# pca10040_sheet3_buttons_and_leds.net
KiCad netlist of a schematic drawn in Altium Designer
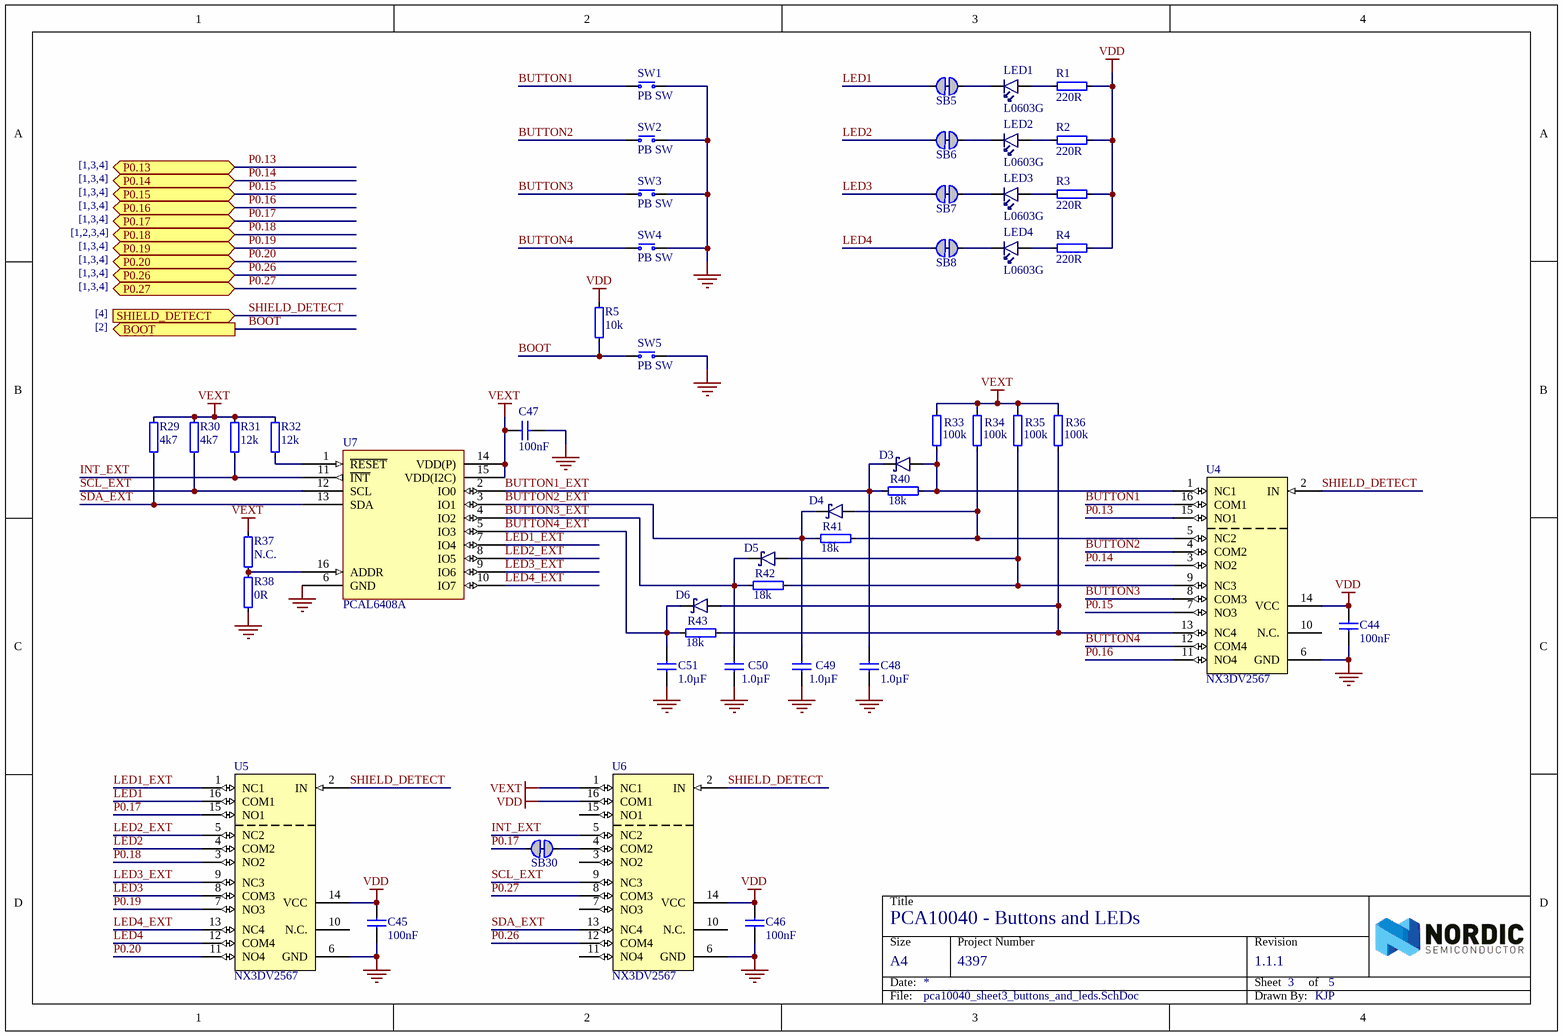
[diagram p0: pca10040_sheet3_buttons_and_leds.SchDoc]

(export (version "E")
  (design (tool "Eeschema 10.0.6"))
  (components
    (comp (ref "C44")
      (value "100nF")
      (footprint "CAPC1005X04L")
      (description "Capacitor, X7R, ±10%")
      (fields (field (name "PART NUMBER") "C0402-100n") (field (name "PUBLISHER") "Nordic Semiconductor"))
      (libsource (lib "Nordic Passive DB") (part "CAP"))
    )
    (comp (ref "C45")
      (value "100nF")
      (footprint "CAPC1005X04L")
      (description "Capacitor, X7R, ±10%")
      (fields (field (name "PART NUMBER") "C0402-100n") (field (name "PUBLISHER") "Nordic Semiconductor"))
      (libsource (lib "Nordic Passive DB") (part "CAP"))
    )
    (comp (ref "C46")
      (value "100nF")
      (footprint "CAPC1005X04L")
      (description "Capacitor, X7R, ±10%")
      (fields (field (name "PART NUMBER") "C0402-100n") (field (name "PUBLISHER") "Nordic Semiconductor"))
      (libsource (lib "Nordic Passive DB") (part "CAP"))
    )
    (comp (ref "C47")
      (value "100nF")
      (footprint "CAPC1005X04L")
      (description "Capacitor, X7R, ±10%")
      (fields (field (name "PART NUMBER") "C0402-100n") (field (name "PUBLISHER") "Nordic Semiconductor"))
      (libsource (lib "Nordic Passive DB") (part "CAP"))
    )
    (comp (ref "C48")
      (value "1.0µF")
      (footprint "CAPC1005X04L")
      (description "Capacitor, X5R, ±5%")
      (fields (field (name "PART NUMBER") "C0402-1µ0") (field (name "PUBLISHER") "Nordic Semiconductor"))
      (libsource (lib "Nordic Passive DB") (part "CAP"))
    )
    (comp (ref "C49")
      (value "1.0µF")
      (footprint "CAPC1005X04L")
      (description "Capacitor, X5R, ±5%")
      (fields (field (name "PART NUMBER") "C0402-1µ0") (field (name "PUBLISHER") "Nordic Semiconductor"))
      (libsource (lib "Nordic Passive DB") (part "CAP"))
    )
    (comp (ref "C50")
      (value "1.0µF")
      (footprint "CAPC1005X04L")
      (description "Capacitor, X5R, ±5%")
      (fields (field (name "PART NUMBER") "C0402-1µ0") (field (name "PUBLISHER") "Nordic Semiconductor"))
      (libsource (lib "Nordic Passive DB") (part "CAP"))
    )
    (comp (ref "C51")
      (value "1.0µF")
      (footprint "CAPC1005X04L")
      (description "Capacitor, X5R, ±5%")
      (fields (field (name "PART NUMBER") "C0402-1µ0") (field (name "PUBLISHER") "Nordic Semiconductor"))
      (libsource (lib "Nordic Passive DB") (part "CAP"))
    )
    (comp (ref "D3")
      (value "1PS79SB30.115")
      (footprint "SOD-523")
      (description "Diode Schottky Vf=0.38, Vr=40V, If=200mA, Ir=500nA")
      (fields (field (name "MANUFACTURER") "NXP") (field (name "PUBLISHER") "Nordic Semiconductor"))
      (libsource (lib "Nordic Discrete DB") (part "D{colon}SCHOTTKY"))
    )
    (comp (ref "D4")
      (value "1PS79SB30.115")
      (footprint "SOD-523")
      (description "Diode Schottky Vf=0.38, Vr=40V, If=200mA, Ir=500nA")
      (fields (field (name "MANUFACTURER") "NXP") (field (name "PUBLISHER") "Nordic Semiconductor"))
      (libsource (lib "Nordic Discrete DB") (part "D{colon}SCHOTTKY"))
    )
    (comp (ref "D5")
      (value "1PS79SB30.115")
      (footprint "SOD-523")
      (description "Diode Schottky Vf=0.38, Vr=40V, If=200mA, Ir=500nA")
      (fields (field (name "MANUFACTURER") "NXP") (field (name "PUBLISHER") "Nordic Semiconductor"))
      (libsource (lib "Nordic Discrete DB") (part "D{colon}SCHOTTKY"))
    )
    (comp (ref "D6")
      (value "1PS79SB30.115")
      (footprint "SOD-523")
      (description "Diode Schottky Vf=0.38, Vr=40V, If=200mA, Ir=500nA")
      (fields (field (name "MANUFACTURER") "NXP") (field (name "PUBLISHER") "Nordic Semiconductor"))
      (libsource (lib "Nordic Discrete DB") (part "D{colon}SCHOTTKY"))
    )
    (comp (ref "LED1")
      (value "L0603G")
      (footprint "LED_0603_G")
      (description "LED SMARTLED GREEN 570NM 0603")
      (fields
        (field (name "PART NUMBER") "LG L29K Smartled Green")
        (field (name "MANUFACTURER") "Multicomp")
        (field (name "PUBLISHER") "Nordic Semiconductor")
      )
      (libsource (lib "Nordic Discrete DB") (part "D{colon}LED"))
    )
    (comp (ref "LED2")
      (value "L0603G")
      (footprint "LED_0603_G")
      (description "LED SMARTLED GREEN 570NM 0603")
      (fields
        (field (name "PART NUMBER") "LG L29K Smartled Green")
        (field (name "MANUFACTURER") "Multicomp")
        (field (name "PUBLISHER") "Nordic Semiconductor")
      )
      (libsource (lib "Nordic Discrete DB") (part "D{colon}LED"))
    )
    (comp (ref "LED3")
      (value "L0603G")
      (footprint "LED_0603_G")
      (description "LED SMARTLED GREEN 570NM 0603")
      (fields
        (field (name "PART NUMBER") "LG L29K Smartled Green")
        (field (name "MANUFACTURER") "Multicomp")
        (field (name "PUBLISHER") "Nordic Semiconductor")
      )
      (libsource (lib "Nordic Discrete DB") (part "D{colon}LED"))
    )
    (comp (ref "LED4")
      (value "L0603G")
      (footprint "LED_0603_G")
      (description "LED SMARTLED GREEN 570NM 0603")
      (fields
        (field (name "PART NUMBER") "LG L29K Smartled Green")
        (field (name "MANUFACTURER") "Multicomp")
        (field (name "PUBLISHER") "Nordic Semiconductor")
      )
      (libsource (lib "Nordic Discrete DB") (part "D{colon}LED"))
    )
    (comp (ref "R1")
      (value "220R")
      (footprint "RESC1005X04L")
      (description "Resistor, ±1%, 0.063W")
      (fields (field (name "PART NUMBER") "R0402-220") (field (name "PUBLISHER") "Nordic Semiconductor"))
      (libsource (lib "Nordic Passive DB") (part "RES_1"))
    )
    (comp (ref "R2")
      (value "220R")
      (footprint "RESC1005X04L")
      (description "Resistor, ±1%, 0.063W")
      (fields (field (name "PART NUMBER") "R0402-220") (field (name "PUBLISHER") "Nordic Semiconductor"))
      (libsource (lib "Nordic Passive DB") (part "RES_1"))
    )
    (comp (ref "R3")
      (value "220R")
      (footprint "RESC1005X04L")
      (description "Resistor, ±1%, 0.063W")
      (fields (field (name "PART NUMBER") "R0402-220") (field (name "PUBLISHER") "Nordic Semiconductor"))
      (libsource (lib "Nordic Passive DB") (part "RES_1"))
    )
    (comp (ref "R4")
      (value "220R")
      (footprint "RESC1005X04L")
      (description "Resistor, ±1%, 0.063W")
      (fields (field (name "PART NUMBER") "R0402-220") (field (name "PUBLISHER") "Nordic Semiconductor"))
      (libsource (lib "Nordic Passive DB") (part "RES_1"))
    )
    (comp (ref "R5")
      (value "10k")
      (footprint "RESC1005X04L")
      (description "Resistor, ±1%, 0.063W")
      (fields (field (name "PART NUMBER") "R0402-10k") (field (name "PUBLISHER") "Nordic Semiconductor"))
      (libsource (lib "Nordic Passive DB") (part "RES_1"))
    )
    (comp (ref "R29")
      (value "4k7")
      (footprint "RESC1005X04L")
      (description "Resistor, ±1%, 0.063W")
      (fields (field (name "PART NUMBER") "R0402-4k7") (field (name "PUBLISHER") "Nordic Semiconductor"))
      (libsource (lib "Nordic Passive DB") (part "RES_1"))
    )
    (comp (ref "R30")
      (value "4k7")
      (footprint "RESC1005X04L")
      (description "Resistor, ±1%, 0.063W")
      (fields (field (name "PART NUMBER") "R0402-4k7") (field (name "PUBLISHER") "Nordic Semiconductor"))
      (libsource (lib "Nordic Passive DB") (part "RES_1"))
    )
    (comp (ref "R31")
      (value "12k")
      (footprint "RESC1005X04L")
      (description "Resistor, ±1%, 0.063W")
      (fields (field (name "PART NUMBER") "R0402-12k") (field (name "PUBLISHER") "Nordic Semiconductor"))
      (libsource (lib "Nordic Passive DB") (part "RES_1"))
    )
    (comp (ref "R32")
      (value "12k")
      (footprint "RESC1005X04L")
      (description "Resistor, ±1%, 0.063W")
      (fields (field (name "PART NUMBER") "R0402-12k") (field (name "PUBLISHER") "Nordic Semiconductor"))
      (libsource (lib "Nordic Passive DB") (part "RES_1"))
    )
    (comp (ref "R33")
      (value "100k")
      (footprint "RESC1005X04L")
      (description "Resistor, ±1%, 0.063W")
      (fields (field (name "PART NUMBER") "R0402-100k") (field (name "PUBLISHER") "Nordic Semiconductor"))
      (libsource (lib "Nordic Passive DB") (part "RES_1"))
    )
    (comp (ref "R34")
      (value "100k")
      (footprint "RESC1005X04L")
      (description "Resistor, ±1%, 0.063W")
      (fields (field (name "PART NUMBER") "R0402-100k") (field (name "PUBLISHER") "Nordic Semiconductor"))
      (libsource (lib "Nordic Passive DB") (part "RES_1"))
    )
    (comp (ref "R35")
      (value "100k")
      (footprint "RESC1005X04L")
      (description "Resistor, ±1%, 0.063W")
      (fields (field (name "PART NUMBER") "R0402-100k") (field (name "PUBLISHER") "Nordic Semiconductor"))
      (libsource (lib "Nordic Passive DB") (part "RES_1"))
    )
    (comp (ref "R36")
      (value "100k")
      (footprint "RESC1005X04L")
      (description "Resistor, ±1%, 0.063W")
      (fields (field (name "PART NUMBER") "R0402-100k") (field (name "PUBLISHER") "Nordic Semiconductor"))
      (libsource (lib "Nordic Passive DB") (part "RES_1"))
    )
    (comp (ref "R37")
      (value "N.C.")
      (footprint "RESC1005X04L")
      (description "Not mounted")
      (fields (field (name "PART NUMBER") "R0402-N.C.") (field (name "PUBLISHER") "Nordic Semiconductor"))
      (libsource (lib "Nordic Passive DB") (part "RES_1"))
    )
    (comp (ref "R38")
      (value "0R")
      (footprint "RESC1005X04L")
      (description "Resistor, ±5%, 0.063W")
      (fields (field (name "PART NUMBER") "R0402-0R") (field (name "PUBLISHER") "Nordic Semiconductor"))
      (libsource (lib "Nordic Passive DB") (part "RES_1"))
    )
    (comp (ref "R40")
      (value "18k")
      (footprint "RESC1005X04L")
      (description "Resistor, ±1%, 0.063W")
      (fields (field (name "PART NUMBER") "R0402-18k") (field (name "PUBLISHER") "Nordic Semiconductor"))
      (libsource (lib "Nordic Passive DB") (part "RES_1"))
    )
    (comp (ref "R41")
      (value "18k")
      (footprint "RESC1005X04L")
      (description "Resistor, ±1%, 0.063W")
      (fields (field (name "PART NUMBER") "R0402-18k") (field (name "PUBLISHER") "Nordic Semiconductor"))
      (libsource (lib "Nordic Passive DB") (part "RES_1"))
    )
    (comp (ref "R42")
      (value "18k")
      (footprint "RESC1005X04L")
      (description "Resistor, ±1%, 0.063W")
      (fields (field (name "PART NUMBER") "R0402-18k") (field (name "PUBLISHER") "Nordic Semiconductor"))
      (libsource (lib "Nordic Passive DB") (part "RES_1"))
    )
    (comp (ref "R43")
      (value "18k")
      (footprint "RESC1005X04L")
      (description "Resistor, ±1%, 0.063W")
      (fields (field (name "PART NUMBER") "R0402-18k") (field (name "PUBLISHER") "Nordic Semiconductor"))
      (libsource (lib "Nordic Passive DB") (part "RES_1"))
    )
    (comp (ref "SB5")
      (value "Solderbridge")
      (footprint "Solderbridge_Shorted")
      (description "Shorted Solderbridge")
      (fields
        (field (name "PART NUMBER") "Solderbridge Shorted")
        (field (name "PUBLISHER") "Nordic Semiconductor")
      )
      (libsource (lib "Nordic Passive DB") (part "SOLDERBRIDGE_SHORTED"))
    )
    (comp (ref "SB6")
      (value "Solderbridge")
      (footprint "Solderbridge_Shorted")
      (description "Shorted Solderbridge")
      (fields
        (field (name "PART NUMBER") "Solderbridge Shorted")
        (field (name "PUBLISHER") "Nordic Semiconductor")
      )
      (libsource (lib "Nordic Passive DB") (part "SOLDERBRIDGE_SHORTED"))
    )
    (comp (ref "SB7")
      (value "Solderbridge")
      (footprint "Solderbridge_Shorted")
      (description "Shorted Solderbridge")
      (fields
        (field (name "PART NUMBER") "Solderbridge Shorted")
        (field (name "PUBLISHER") "Nordic Semiconductor")
      )
      (libsource (lib "Nordic Passive DB") (part "SOLDERBRIDGE_SHORTED"))
    )
    (comp (ref "SB8")
      (value "Solderbridge")
      (footprint "Solderbridge_Shorted")
      (description "Shorted Solderbridge")
      (fields
        (field (name "PART NUMBER") "Solderbridge Shorted")
        (field (name "PUBLISHER") "Nordic Semiconductor")
      )
      (libsource (lib "Nordic Passive DB") (part "SOLDERBRIDGE_SHORTED"))
    )
    (comp (ref "SB30")
      (value "Solderbridge")
      (footprint "Solderbridge_Shorted")
      (description "Shorted Solderbridge")
      (fields
        (field (name "PART NUMBER") "Solderbridge Shorted")
        (field (name "PUBLISHER") "Nordic Semiconductor")
      )
      (libsource (lib "Nordic Passive DB") (part "SOLDERBRIDGE_SHORTED"))
    )
    (comp (ref "SW1")
      (value "PB SW")
      (footprint "Switch-PB-6.2x6.3mm-SMD")
      (description "Tactile Switch, SPNO, SMD, 160gf, 6.2x6.3x2.5mm")
      (fields
        (field (name "PART NUMBER") "Switch-PB-6.2x6.3mm-SMD")
        (field (name "MANUFACTURER") "Dailywell")
        (field (name "PUBLISHER") "Nordic Semiconductor")
      )
      (libsource (lib "Nordic Discrete DB") (part "SW-PB"))
    )
    (comp (ref "SW2")
      (value "PB SW")
      (footprint "Switch-PB-6.2x6.3mm-SMD")
      (description "Tactile Switch, SPNO, SMD, 160gf, 6.2x6.3x2.5mm")
      (fields
        (field (name "PART NUMBER") "Switch-PB-6.2x6.3mm-SMD")
        (field (name "MANUFACTURER") "Dailywell")
        (field (name "PUBLISHER") "Nordic Semiconductor")
      )
      (libsource (lib "Nordic Discrete DB") (part "SW-PB"))
    )
    (comp (ref "SW3")
      (value "PB SW")
      (footprint "Switch-PB-6.2x6.3mm-SMD")
      (description "Tactile Switch, SPNO, SMD, 160gf, 6.2x6.3x2.5mm")
      (fields
        (field (name "PART NUMBER") "Switch-PB-6.2x6.3mm-SMD")
        (field (name "MANUFACTURER") "Dailywell")
        (field (name "PUBLISHER") "Nordic Semiconductor")
      )
      (libsource (lib "Nordic Discrete DB") (part "SW-PB"))
    )
    (comp (ref "SW4")
      (value "PB SW")
      (footprint "Switch-PB-6.2x6.3mm-SMD")
      (description "Tactile Switch, SPNO, SMD, 160gf, 6.2x6.3x2.5mm")
      (fields
        (field (name "PART NUMBER") "Switch-PB-6.2x6.3mm-SMD")
        (field (name "MANUFACTURER") "Dailywell")
        (field (name "PUBLISHER") "Nordic Semiconductor")
      )
      (libsource (lib "Nordic Discrete DB") (part "SW-PB"))
    )
    (comp (ref "SW5")
      (value "PB SW")
      (footprint "Switch-PB-6.2x6.3mm-SMD")
      (description "Tactile Switch, SPNO, SMD, 160gf, 6.2x6.3x2.5mm")
      (fields
        (field (name "PART NUMBER") "Switch-PB-6.2x6.3mm-SMD")
        (field (name "MANUFACTURER") "Dailywell")
        (field (name "PUBLISHER") "Nordic Semiconductor")
      )
      (libsource (lib "Nordic Discrete DB") (part "SW-PB"))
    )
    (comp (ref "U4")
      (value "NX3DV2567")
      (footprint "XQFN40P180X260X50-16N")
      (description "Low-ohmic four-pole double-throw analog switch")
      (fields
        (field (name "PART NUMBER") "NX3DV2567GU")
        (field (name "MANUFACTURER") "NXP Semiconductors")
        (field (name "PUBLISHER") "Nordic Semiconductor")
      )
      (libsource (lib "Nordic Active DB") (part "NX3DV2567"))
    )
    (comp (ref "U5")
      (value "NX3DV2567")
      (footprint "XQFN40P180X260X50-16N")
      (description "Low-ohmic four-pole double-throw analog switch")
      (fields
        (field (name "PART NUMBER") "NX3DV2567GU")
        (field (name "MANUFACTURER") "NXP Semiconductors")
        (field (name "PUBLISHER") "Nordic Semiconductor")
      )
      (libsource (lib "Nordic Active DB") (part "NX3DV2567"))
    )
    (comp (ref "U6")
      (value "NX3DV2567")
      (footprint "XQFN40P180X260X50-16N")
      (description "Low-ohmic four-pole double-throw analog switch")
      (fields
        (field (name "PART NUMBER") "NX3DV2567GU")
        (field (name "MANUFACTURER") "NXP Semiconductors")
        (field (name "PUBLISHER") "Nordic Semiconductor")
      )
      (libsource (lib "Nordic Active DB") (part "NX3DV2567"))
    )
    (comp (ref "U7")
      (value "PCAL6408A")
      (footprint "XQFN40P180X260X50-16N")
      (description "8-bit I2C-bus I/O expander with interrupt output")
      (fields
        (field (name "PART NUMBER") "PCAL6408AHK")
        (field (name "MANUFACTURER") "NXP Semiconductors")
        (field (name "PUBLISHER") "Nordic Semiconductor")
      )
      (libsource (lib "Nordic Active DB") (part "PCAL6408AHK"))
    )
  )
  (nets
    (net (code "1") (name "/BOOT") (class "Default")
      (node (ref "R5") (pin "1") (pinfunction "1_1") (pintype "passive"))
      (node (ref "SW5") (pin "2") (pinfunction "COM_2") (pintype "passive"))
    )
    (net (code "2") (name "/BUTTON1") (class "Default")
      (node (ref "SW1") (pin "2") (pinfunction "COM_2") (pintype "passive"))
      (node (ref "U4") (pin "16") (pinfunction "COM1_16") (pintype "bidirectional"))
    )
    (net (code "3") (name "/BUTTON1_EXT") (class "Default")
      (node (ref "C48") (pin "1") (pinfunction "1_1") (pintype "passive"))
      (node (ref "D3") (pin "3") (pinfunction "C_3") (pintype "passive"))
      (node (ref "R40") (pin "1") (pinfunction "1_1") (pintype "passive"))
      (node (ref "U7") (pin "2") (pinfunction "IO0_2") (pintype "bidirectional"))
    )
    (net (code "4") (name "/BUTTON2") (class "Default")
      (node (ref "SW2") (pin "2") (pinfunction "COM_2") (pintype "passive"))
      (node (ref "U4") (pin "4") (pinfunction "COM2_4") (pintype "bidirectional"))
    )
    (net (code "5") (name "/BUTTON2_EXT") (class "Default")
      (node (ref "C49") (pin "2") (pinfunction "2_2") (pintype "passive"))
      (node (ref "D4") (pin "3") (pinfunction "C_3") (pintype "passive"))
      (node (ref "R41") (pin "1") (pinfunction "1_1") (pintype "passive"))
      (node (ref "U7") (pin "3") (pinfunction "IO1_3") (pintype "bidirectional"))
    )
    (net (code "6") (name "/BUTTON3") (class "Default")
      (node (ref "SW3") (pin "2") (pinfunction "COM_2") (pintype "passive"))
      (node (ref "U4") (pin "8") (pinfunction "COM3_8") (pintype "bidirectional"))
    )
    (net (code "7") (name "/BUTTON3_EXT") (class "Default")
      (node (ref "C50") (pin "2") (pinfunction "2_2") (pintype "passive"))
      (node (ref "D5") (pin "3") (pinfunction "C_3") (pintype "passive"))
      (node (ref "R42") (pin "1") (pinfunction "1_1") (pintype "passive"))
      (node (ref "U7") (pin "4") (pinfunction "IO2_4") (pintype "bidirectional"))
    )
    (net (code "8") (name "/BUTTON4") (class "Default")
      (node (ref "SW4") (pin "2") (pinfunction "COM_2") (pintype "passive"))
      (node (ref "U4") (pin "12") (pinfunction "COM4_12") (pintype "bidirectional"))
    )
    (net (code "9") (name "/BUTTON4_EXT") (class "Default")
      (node (ref "C51") (pin "1") (pinfunction "1_1") (pintype "passive"))
      (node (ref "D6") (pin "3") (pinfunction "C_3") (pintype "passive"))
      (node (ref "R43") (pin "1") (pinfunction "1_1") (pintype "passive"))
      (node (ref "U7") (pin "5") (pinfunction "IO3_5") (pintype "bidirectional"))
    )
    (net (code "10") (name "/INT_EXT") (class "Default")
      (node (ref "R31") (pin "1") (pinfunction "1_1") (pintype "passive"))
      (node (ref "U6") (pin "5") (pinfunction "NC2_5") (pintype "bidirectional"))
      (node (ref "U7") (pin "11") (pinfunction "~{INT}_11") (pintype "output"))
    )
    (net (code "11") (name "/LED1") (class "Default")
      (node (ref "SB5") (pin "1") (pinfunction "0_1") (pintype "passive"))
      (node (ref "U5") (pin "16") (pinfunction "COM1_16") (pintype "bidirectional"))
    )
    (net (code "12") (name "/LED1_EXT") (class "Default")
      (node (ref "U5") (pin "1") (pinfunction "NC1_1") (pintype "bidirectional"))
      (node (ref "U7") (pin "7") (pinfunction "IO4_7") (pintype "bidirectional"))
    )
    (net (code "13") (name "/LED2") (class "Default")
      (node (ref "SB6") (pin "1") (pinfunction "0_1") (pintype "passive"))
      (node (ref "U5") (pin "4") (pinfunction "COM2_4") (pintype "bidirectional"))
    )
    (net (code "14") (name "/LED2_EXT") (class "Default")
      (node (ref "U5") (pin "5") (pinfunction "NC2_5") (pintype "bidirectional"))
      (node (ref "U7") (pin "8") (pinfunction "IO5_8") (pintype "bidirectional"))
    )
    (net (code "15") (name "/LED3") (class "Default")
      (node (ref "SB7") (pin "1") (pinfunction "0_1") (pintype "passive"))
      (node (ref "U5") (pin "8") (pinfunction "COM3_8") (pintype "bidirectional"))
    )
    (net (code "16") (name "/LED3_EXT") (class "Default")
      (node (ref "U5") (pin "9") (pinfunction "NC3_9") (pintype "bidirectional"))
      (node (ref "U7") (pin "9") (pinfunction "IO6_9") (pintype "bidirectional"))
    )
    (net (code "17") (name "/LED4") (class "Default")
      (node (ref "SB8") (pin "1") (pinfunction "0_1") (pintype "passive"))
      (node (ref "U5") (pin "12") (pinfunction "COM4_12") (pintype "bidirectional"))
    )
    (net (code "18") (name "/LED4_EXT") (class "Default")
      (node (ref "U5") (pin "13") (pinfunction "NC4_13") (pintype "bidirectional"))
      (node (ref "U7") (pin "10") (pinfunction "IO7_10") (pintype "bidirectional"))
    )
    (net (code "19") (name "/P0.13") (class "Default")
      (node (ref "U4") (pin "15") (pinfunction "NO1_15") (pintype "bidirectional"))
    )
    (net (code "20") (name "/P0.14") (class "Default")
      (node (ref "U4") (pin "3") (pinfunction "NO2_3") (pintype "bidirectional"))
    )
    (net (code "21") (name "/P0.15") (class "Default")
      (node (ref "U4") (pin "7") (pinfunction "NO3_7") (pintype "bidirectional"))
    )
    (net (code "22") (name "/P0.16") (class "Default")
      (node (ref "U4") (pin "11") (pinfunction "NO4_11") (pintype "bidirectional"))
    )
    (net (code "23") (name "/P0.17") (class "Default")
      (node (ref "SB30") (pin "1") (pinfunction "0_1") (pintype "passive"))
      (node (ref "U5") (pin "15") (pinfunction "NO1_15") (pintype "bidirectional"))
    )
    (net (code "24") (name "/P0.18") (class "Default")
      (node (ref "U5") (pin "3") (pinfunction "NO2_3") (pintype "bidirectional"))
    )
    (net (code "25") (name "/P0.19") (class "Default")
      (node (ref "U5") (pin "7") (pinfunction "NO3_7") (pintype "bidirectional"))
    )
    (net (code "26") (name "/P0.20") (class "Default")
      (node (ref "U5") (pin "11") (pinfunction "NO4_11") (pintype "bidirectional"))
    )
    (net (code "27") (name "/P0.26") (class "Default")
      (node (ref "U6") (pin "12") (pinfunction "COM4_12") (pintype "bidirectional"))
    )
    (net (code "28") (name "/P0.27") (class "Default")
      (node (ref "U6") (pin "8") (pinfunction "COM3_8") (pintype "bidirectional"))
    )
    (net (code "29") (name "/SCL_EXT") (class "Default")
      (node (ref "R30") (pin "1") (pinfunction "1_1") (pintype "passive"))
      (node (ref "U6") (pin "9") (pinfunction "NC3_9") (pintype "bidirectional"))
      (node (ref "U7") (pin "12") (pinfunction "SCL_12") (pintype "power_in"))
    )
    (net (code "30") (name "/SDA_EXT") (class "Default")
      (node (ref "R29") (pin "1") (pinfunction "1_1") (pintype "passive"))
      (node (ref "U6") (pin "13") (pinfunction "NC4_13") (pintype "bidirectional"))
      (node (ref "U7") (pin "13") (pinfunction "SDA_13") (pintype "passive"))
    )
    (net (code "31") (name "/SHIELD_DETECT") (class "Default")
      (node (ref "U4") (pin "2") (pinfunction "IN_2") (pintype "input"))
      (node (ref "U5") (pin "2") (pinfunction "IN_2") (pintype "input"))
      (node (ref "U6") (pin "2") (pinfunction "IN_2") (pintype "input"))
    )
    (net (code "32") (name "GND") (class "Default")
      (node (ref "C44") (pin "1") (pinfunction "1_1") (pintype "passive"))
      (node (ref "C45") (pin "1") (pinfunction "1_1") (pintype "passive"))
      (node (ref "C46") (pin "1") (pinfunction "1_1") (pintype "passive"))
      (node (ref "C47") (pin "1") (pinfunction "1_1") (pintype "passive"))
      (node (ref "C48") (pin "2") (pinfunction "2_2") (pintype "passive"))
      (node (ref "C49") (pin "1") (pinfunction "1_1") (pintype "passive"))
      (node (ref "C50") (pin "1") (pinfunction "1_1") (pintype "passive"))
      (node (ref "C51") (pin "2") (pinfunction "2_2") (pintype "passive"))
      (node (ref "R38") (pin "1") (pinfunction "1_1") (pintype "passive"))
      (node (ref "SW1") (pin "1") (pinfunction "N.O_1") (pintype "passive"))
      (node (ref "SW2") (pin "1") (pinfunction "N.O_1") (pintype "passive"))
      (node (ref "SW3") (pin "1") (pinfunction "N.O_1") (pintype "passive"))
      (node (ref "SW4") (pin "1") (pinfunction "N.O_1") (pintype "passive"))
      (node (ref "SW5") (pin "1") (pinfunction "N.O_1") (pintype "passive"))
      (node (ref "U4") (pin "6") (pinfunction "GND_6") (pintype "power_in"))
      (node (ref "U5") (pin "6") (pinfunction "GND_6") (pintype "power_in"))
      (node (ref "U6") (pin "6") (pinfunction "GND_6") (pintype "power_in"))
      (node (ref "U7") (pin "6") (pinfunction "GND_6") (pintype "power_in"))
    )
    (net (code "33") (name "Net-(D3-A)") (class "Default")
      (node (ref "D3") (pin "1") (pinfunction "A_1") (pintype "passive"))
      (node (ref "R33") (pin "1") (pinfunction "1_1") (pintype "passive"))
      (node (ref "R40") (pin "2") (pinfunction "2_2") (pintype "passive"))
      (node (ref "U4") (pin "1") (pinfunction "NC1_1") (pintype "bidirectional"))
    )
    (net (code "34") (name "Net-(D4-A)") (class "Default")
      (node (ref "D4") (pin "1") (pinfunction "A_1") (pintype "passive"))
      (node (ref "R34") (pin "1") (pinfunction "1_1") (pintype "passive"))
      (node (ref "R41") (pin "2") (pinfunction "2_2") (pintype "passive"))
      (node (ref "U4") (pin "5") (pinfunction "NC2_5") (pintype "bidirectional"))
    )
    (net (code "35") (name "Net-(D5-A)") (class "Default")
      (node (ref "D5") (pin "1") (pinfunction "A_1") (pintype "passive"))
      (node (ref "R35") (pin "1") (pinfunction "1_1") (pintype "passive"))
      (node (ref "R42") (pin "2") (pinfunction "2_2") (pintype "passive"))
      (node (ref "U4") (pin "9") (pinfunction "NC3_9") (pintype "bidirectional"))
    )
    (net (code "36") (name "Net-(D6-A)") (class "Default")
      (node (ref "D6") (pin "1") (pinfunction "A_1") (pintype "passive"))
      (node (ref "R36") (pin "1") (pinfunction "1_1") (pintype "passive"))
      (node (ref "R43") (pin "2") (pinfunction "2_2") (pintype "passive"))
      (node (ref "U4") (pin "13") (pinfunction "NC4_13") (pintype "bidirectional"))
    )
    (net (code "37") (name "Net-(LED1-A)") (class "Default")
      (node (ref "LED1") (pin "2") (pinfunction "A_2") (pintype "passive"))
      (node (ref "R1") (pin "1") (pinfunction "1_1") (pintype "passive"))
    )
    (net (code "38") (name "Net-(LED1-C)") (class "Default")
      (node (ref "LED1") (pin "1") (pinfunction "C_1") (pintype "passive"))
      (node (ref "SB5") (pin "2") (pinfunction "1_2") (pintype "passive"))
    )
    (net (code "39") (name "Net-(LED2-A)") (class "Default")
      (node (ref "LED2") (pin "2") (pinfunction "A_2") (pintype "passive"))
      (node (ref "R2") (pin "1") (pinfunction "1_1") (pintype "passive"))
    )
    (net (code "40") (name "Net-(LED2-C)") (class "Default")
      (node (ref "LED2") (pin "1") (pinfunction "C_1") (pintype "passive"))
      (node (ref "SB6") (pin "2") (pinfunction "1_2") (pintype "passive"))
    )
    (net (code "41") (name "Net-(LED3-A)") (class "Default")
      (node (ref "LED3") (pin "2") (pinfunction "A_2") (pintype "passive"))
      (node (ref "R3") (pin "1") (pinfunction "1_1") (pintype "passive"))
    )
    (net (code "42") (name "Net-(LED3-C)") (class "Default")
      (node (ref "LED3") (pin "1") (pinfunction "C_1") (pintype "passive"))
      (node (ref "SB7") (pin "2") (pinfunction "1_2") (pintype "passive"))
    )
    (net (code "43") (name "Net-(LED4-A)") (class "Default")
      (node (ref "LED4") (pin "2") (pinfunction "A_2") (pintype "passive"))
      (node (ref "R4") (pin "1") (pinfunction "1_1") (pintype "passive"))
    )
    (net (code "44") (name "Net-(LED4-C)") (class "Default")
      (node (ref "LED4") (pin "1") (pinfunction "C_1") (pintype "passive"))
      (node (ref "SB8") (pin "2") (pinfunction "1_2") (pintype "passive"))
    )
    (net (code "45") (name "Net-(SB30-1)") (class "Default")
      (node (ref "SB30") (pin "2") (pinfunction "1_2") (pintype "passive"))
      (node (ref "U6") (pin "4") (pinfunction "COM2_4") (pintype "bidirectional"))
    )
    (net (code "46") (name "Net-(U7-ADDR)") (class "Default")
      (node (ref "R37") (pin "1") (pinfunction "1_1") (pintype "passive"))
      (node (ref "R38") (pin "2") (pinfunction "2_2") (pintype "passive"))
      (node (ref "U7") (pin "16") (pinfunction "ADDR_16") (pintype "input"))
    )
    (net (code "47") (name "Net-(U7-~{RESET})") (class "Default")
      (node (ref "R32") (pin "1") (pinfunction "1_1") (pintype "passive"))
      (node (ref "U7") (pin "1") (pinfunction "~{RESET}_1") (pintype "input"))
    )
    (net (code "48") (name "VDD") (class "Default")
      (node (ref "C44") (pin "2") (pinfunction "2_2") (pintype "passive"))
      (node (ref "C45") (pin "2") (pinfunction "2_2") (pintype "passive"))
      (node (ref "C46") (pin "2") (pinfunction "2_2") (pintype "passive"))
      (node (ref "R1") (pin "2") (pinfunction "2_2") (pintype "passive"))
      (node (ref "R2") (pin "2") (pinfunction "2_2") (pintype "passive"))
      (node (ref "R3") (pin "2") (pinfunction "2_2") (pintype "passive"))
      (node (ref "R4") (pin "2") (pinfunction "2_2") (pintype "passive"))
      (node (ref "R5") (pin "2") (pinfunction "2_2") (pintype "passive"))
      (node (ref "U4") (pin "14") (pinfunction "VCC_14") (pintype "power_in"))
      (node (ref "U5") (pin "14") (pinfunction "VCC_14") (pintype "power_in"))
      (node (ref "U6") (pin "14") (pinfunction "VCC_14") (pintype "power_in"))
      (node (ref "U6") (pin "16") (pinfunction "COM1_16") (pintype "bidirectional"))
    )
    (net (code "49") (name "VEXT") (class "Default")
      (node (ref "C47") (pin "2") (pinfunction "2_2") (pintype "passive"))
      (node (ref "R29") (pin "2") (pinfunction "2_2") (pintype "passive"))
      (node (ref "R30") (pin "2") (pinfunction "2_2") (pintype "passive"))
      (node (ref "R31") (pin "2") (pinfunction "2_2") (pintype "passive"))
      (node (ref "R32") (pin "2") (pinfunction "2_2") (pintype "passive"))
      (node (ref "R33") (pin "2") (pinfunction "2_2") (pintype "passive"))
      (node (ref "R34") (pin "2") (pinfunction "2_2") (pintype "passive"))
      (node (ref "R35") (pin "2") (pinfunction "2_2") (pintype "passive"))
      (node (ref "R36") (pin "2") (pinfunction "2_2") (pintype "passive"))
      (node (ref "R37") (pin "2") (pinfunction "2_2") (pintype "passive"))
      (node (ref "U6") (pin "1") (pinfunction "NC1_1") (pintype "bidirectional"))
      (node (ref "U7") (pin "14") (pinfunction "VDD(P)_14") (pintype "power_in"))
      (node (ref "U7") (pin "15") (pinfunction "VDD(I2C)_15") (pintype "power_in"))
    )
    (net (code "50") (name "unconnected-(U4-N.C.-Pad10)") (class "Default")
      (node (ref "U4") (pin "10") (pinfunction "N.C._10") (pintype "passive"))
    )
    (net (code "51") (name "unconnected-(U5-N.C.-Pad10)") (class "Default")
      (node (ref "U5") (pin "10") (pinfunction "N.C._10") (pintype "passive"))
    )
    (net (code "52") (name "unconnected-(U6-N.C.-Pad10)") (class "Default")
      (node (ref "U6") (pin "10") (pinfunction "N.C._10") (pintype "passive"))
    )
    (net (code "53") (name "unconnected-(U6-NO1-Pad15)") (class "Default")
      (node (ref "U6") (pin "15") (pinfunction "NO1_15") (pintype "bidirectional"))
    )
    (net (code "54") (name "unconnected-(U6-NO2-Pad3)") (class "Default")
      (node (ref "U6") (pin "3") (pinfunction "NO2_3") (pintype "bidirectional"))
    )
    (net (code "55") (name "unconnected-(U6-NO3-Pad7)") (class "Default")
      (node (ref "U6") (pin "7") (pinfunction "NO3_7") (pintype "bidirectional"))
    )
    (net (code "56") (name "unconnected-(U6-NO4-Pad11)") (class "Default")
      (node (ref "U6") (pin "11") (pinfunction "NO4_11") (pintype "bidirectional"))
    )
  )
)
